# antenas_mod.net
KiCad netlist of a schematic drawn in EAGLE
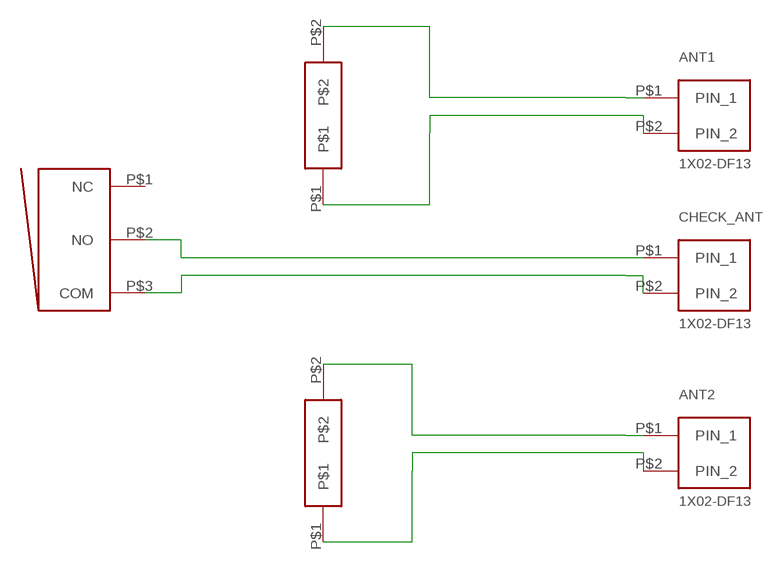
[diagram p0: schematic, sheet 1]

(export (version "E")
  (design (tool "Eeschema 10.0.6"))
  (components
    (comp (ref "ANT1")
      (value "1X02-DF13")
      (footprint "eagle-import:DF-13")
      (libsource (lib "eagle-import") (part "1X02-DF13"))
    )
    (comp (ref "ANT2")
      (value "1X02-DF13")
      (footprint "eagle-import:DF-13")
      (libsource (lib "eagle-import") (part "1X02-DF13"))
    )
    (comp (ref "CHECK_ANT")
      (value "1X02-DF13")
      (footprint "eagle-import:DF-13")
      (libsource (lib "eagle-import") (part "1X02-DF13"))
    )
    (comp (ref "U$1")
      (value "SWITCH_ANT_TRHU")
      (footprint "eagle-import:3_HOLE")
      (libsource (lib "eagle-import") (part "SWITCH_ANT_TRHU"))
    )
    (comp (ref "U$5")
      (value "RPOWER")
      (footprint "eagle-import:RPOWER")
      (libsource (lib "eagle-import") (part "RPOWER"))
    )
    (comp (ref "U$6")
      (value "RPOWER")
      (footprint "eagle-import:RPOWER")
      (libsource (lib "eagle-import") (part "RPOWER"))
    )
  )
  (nets
    (net (code "1") (name "Net-(ANT1-PIN_1)") (class "Default")
      (node (ref "ANT1") (pin "P$1") (pinfunction "PIN_1_P$1") (pintype "bidirectional"))
      (node (ref "U$5") (pin "P$2") (pinfunction "P$2_P$2") (pintype "bidirectional"))
    )
    (net (code "2") (name "Net-(ANT1-PIN_2)") (class "Default")
      (node (ref "ANT1") (pin "P$2") (pinfunction "PIN_2_P$2") (pintype "bidirectional"))
      (node (ref "U$5") (pin "P$1") (pinfunction "P$1_P$1") (pintype "bidirectional"))
    )
    (net (code "3") (name "Net-(ANT2-PIN_1)") (class "Default")
      (node (ref "ANT2") (pin "P$1") (pinfunction "PIN_1_P$1") (pintype "bidirectional"))
      (node (ref "U$6") (pin "P$2") (pinfunction "P$2_P$2") (pintype "bidirectional"))
    )
    (net (code "4") (name "Net-(ANT2-PIN_2)") (class "Default")
      (node (ref "ANT2") (pin "P$2") (pinfunction "PIN_2_P$2") (pintype "bidirectional"))
      (node (ref "U$6") (pin "P$1") (pinfunction "P$1_P$1") (pintype "bidirectional"))
    )
    (net (code "5") (name "Net-(CHECK_ANT-PIN_1)") (class "Default")
      (node (ref "CHECK_ANT") (pin "P$1") (pinfunction "PIN_1_P$1") (pintype "bidirectional"))
      (node (ref "U$1") (pin "P$2") (pinfunction "NO_P$2") (pintype "bidirectional"))
    )
    (net (code "6") (name "Net-(CHECK_ANT-PIN_2)") (class "Default")
      (node (ref "CHECK_ANT") (pin "P$2") (pinfunction "PIN_2_P$2") (pintype "bidirectional"))
      (node (ref "U$1") (pin "P$3") (pinfunction "COM_P$3") (pintype "bidirectional"))
    )
    (net (code "7") (name "unconnected-(U$1-NC-PadP$1)") (class "Default")
      (node (ref "U$1") (pin "P$1") (pinfunction "NC_P$1") (pintype "bidirectional"))
    )
  )
)
